# stm32.net
KiCad netlist of a schematic drawn in Altium Designer
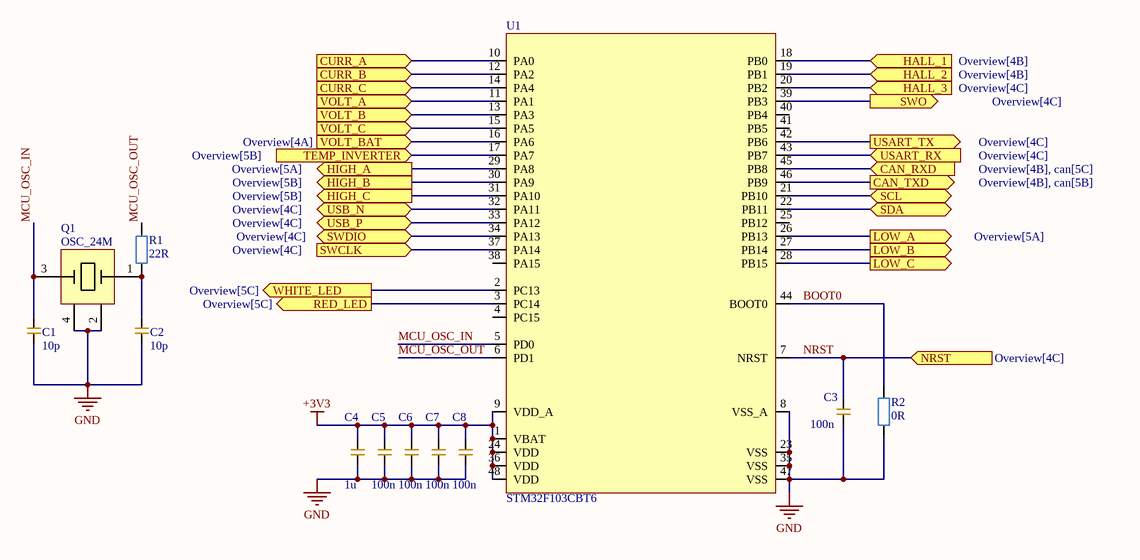
[diagram p0: stm32.SchDoc]

(export (version "E")
  (design (tool "Eeschema 10.0.6"))
  (components
    (comp (ref "C1")
      (value "10p")
      (footprint "CAP_0603")
      (description "Multilayer Ceramic Capacitors MLCC - SMD/SMT ROHS")
      (libsource (lib "Passive") (part "CAP_0603"))
    )
    (comp (ref "C2")
      (value "10p")
      (footprint "CAP_0603")
      (description "Multilayer Ceramic Capacitors MLCC - SMD/SMT ROHS")
      (libsource (lib "Passive") (part "CAP_0603"))
    )
    (comp (ref "C3")
      (value "100n")
      (footprint "CAP_0603")
      (description "Multilayer Ceramic Capacitors MLCC - SMD/SMT ROHS")
      (libsource (lib "Passive") (part "CAP_0603"))
    )
    (comp (ref "C4")
      (value "1u")
      (footprint "CAP_0603")
      (description "Multilayer Ceramic Capacitors MLCC - SMD/SMT ROHS")
      (libsource (lib "Passive") (part "CAP_0603"))
    )
    (comp (ref "C5")
      (value "100n")
      (footprint "CAP_0603")
      (description "Multilayer Ceramic Capacitors MLCC - SMD/SMT ROHS")
      (libsource (lib "Passive") (part "CAP_0603"))
    )
    (comp (ref "C6")
      (value "100n")
      (footprint "CAP_0603")
      (description "Multilayer Ceramic Capacitors MLCC - SMD/SMT ROHS")
      (libsource (lib "Passive") (part "CAP_0603"))
    )
    (comp (ref "C7")
      (value "100n")
      (footprint "CAP_0603")
      (description "Multilayer Ceramic Capacitors MLCC - SMD/SMT ROHS")
      (libsource (lib "Passive") (part "CAP_0603"))
    )
    (comp (ref "C8")
      (value "100n")
      (footprint "CAP_0603")
      (description "Multilayer Ceramic Capacitors MLCC - SMD/SMT ROHS")
      (libsource (lib "Passive") (part "CAP_0603"))
    )
    (comp (ref "Q1")
      (value "OSC_24M")
      (footprint "OSC_24M")
      (description "Crystal 24Mhz")
      (fields (field (name "MANUFACTURER PART") "X322524MOB4SI"))
      (libsource (lib "ICs") (part "OSC_24M"))
    )
    (comp (ref "R1")
      (value "22R")
      (footprint "RES_0603")
      (description "100mW Thick Film Resistors")
      (libsource (lib "Passive") (part "RES_0603"))
    )
    (comp (ref "R2")
      (value "0R")
      (footprint "RES_0603")
      (description "100mW Thick Film Resistors")
      (libsource (lib "Passive") (part "RES_0603"))
    )
    (comp (ref "U1")
      (value "STM32F103CBT6")
      (footprint "STM32F103CBT6")
      (fields (field (name "MFR.") "STMicroelectronics"))
      (libsource (lib "ICs") (part "STM32F103CBT6"))
    )
  )
  (nets
    (net (code "1") (name "+3V3") (class "Default")
      (node (ref "C4") (pin "2") (pintype "passive"))
      (node (ref "C5") (pin "2") (pintype "passive"))
      (node (ref "C6") (pin "2") (pintype "passive"))
      (node (ref "C7") (pin "2") (pintype "passive"))
      (node (ref "C8") (pin "2") (pintype "passive"))
      (node (ref "U1") (pin "1") (pinfunction "VBAT_1") (pintype "passive"))
      (node (ref "U1") (pin "24") (pinfunction "VDD_24") (pintype "passive"))
      (node (ref "U1") (pin "36") (pinfunction "VDD_36") (pintype "passive"))
      (node (ref "U1") (pin "48") (pinfunction "VDD_48") (pintype "passive"))
      (node (ref "U1") (pin "9") (pinfunction "VDD_A_9") (pintype "passive"))
    )
    (net (code "2") (name "/BOOT0") (class "Default")
      (node (ref "R2") (pin "2") (pintype "passive"))
      (node (ref "U1") (pin "44") (pinfunction "BOOT0_44") (pintype "passive"))
    )
    (net (code "3") (name "/CAN_RXD") (class "Default")
      (node (ref "U1") (pin "45") (pinfunction "PB8_45") (pintype "passive"))
    )
    (net (code "4") (name "/CAN_TXD") (class "Default")
      (node (ref "U1") (pin "46") (pinfunction "PB9_46") (pintype "passive"))
    )
    (net (code "5") (name "/CURR_A") (class "Default")
      (node (ref "U1") (pin "10") (pinfunction "PA0_10") (pintype "passive"))
    )
    (net (code "6") (name "/CURR_B") (class "Default")
      (node (ref "U1") (pin "12") (pinfunction "PA2_12") (pintype "passive"))
    )
    (net (code "7") (name "/CURR_C") (class "Default")
      (node (ref "U1") (pin "14") (pinfunction "PA4_14") (pintype "passive"))
    )
    (net (code "8") (name "/HALL_1") (class "Default")
      (node (ref "U1") (pin "18") (pinfunction "PB0_18") (pintype "passive"))
    )
    (net (code "9") (name "/HALL_2") (class "Default")
      (node (ref "U1") (pin "19") (pinfunction "PB1_19") (pintype "passive"))
    )
    (net (code "10") (name "/HALL_3") (class "Default")
      (node (ref "U1") (pin "20") (pinfunction "PB2_20") (pintype "passive"))
    )
    (net (code "11") (name "/HIGH_A") (class "Default")
      (node (ref "U1") (pin "29") (pinfunction "PA8_29") (pintype "passive"))
    )
    (net (code "12") (name "/HIGH_B") (class "Default")
      (node (ref "U1") (pin "30") (pinfunction "PA9_30") (pintype "passive"))
    )
    (net (code "13") (name "/HIGH_C") (class "Default")
      (node (ref "U1") (pin "31") (pinfunction "PA10_31") (pintype "passive"))
    )
    (net (code "14") (name "/LOW_A") (class "Default")
      (node (ref "U1") (pin "26") (pinfunction "PB13_26") (pintype "passive"))
    )
    (net (code "15") (name "/LOW_B") (class "Default")
      (node (ref "U1") (pin "27") (pinfunction "PB14_27") (pintype "passive"))
    )
    (net (code "16") (name "/LOW_C") (class "Default")
      (node (ref "U1") (pin "28") (pinfunction "PB15_28") (pintype "passive"))
    )
    (net (code "17") (name "/MCU_OSC_IN") (class "Default")
      (node (ref "C1") (pin "2") (pintype "passive"))
      (node (ref "Q1") (pin "3") (pintype "passive"))
      (node (ref "U1") (pin "5") (pinfunction "PD0_5") (pintype "passive"))
    )
    (net (code "18") (name "/MCU_OSC_OUT") (class "Default")
      (node (ref "R1") (pin "2") (pintype "passive"))
      (node (ref "U1") (pin "6") (pinfunction "PD1_6") (pintype "passive"))
    )
    (net (code "19") (name "/NRST") (class "Default")
      (node (ref "C3") (pin "2") (pintype "passive"))
      (node (ref "U1") (pin "7") (pinfunction "NRST_7") (pintype "passive"))
    )
    (net (code "20") (name "/RED_LED") (class "Default")
      (node (ref "U1") (pin "3") (pinfunction "PC14_3") (pintype "passive"))
    )
    (net (code "21") (name "/SCL") (class "Default")
      (node (ref "U1") (pin "21") (pinfunction "PB10_21") (pintype "passive"))
    )
    (net (code "22") (name "/SDA") (class "Default")
      (node (ref "U1") (pin "22") (pinfunction "PB11_22") (pintype "passive"))
    )
    (net (code "23") (name "/SWCLK") (class "Default")
      (node (ref "U1") (pin "37") (pinfunction "PA14_37") (pintype "passive"))
    )
    (net (code "24") (name "/SWDIO") (class "Default")
      (node (ref "U1") (pin "34") (pinfunction "PA13_34") (pintype "passive"))
    )
    (net (code "25") (name "/SWO") (class "Default")
      (node (ref "U1") (pin "39") (pinfunction "PB3_39") (pintype "passive"))
    )
    (net (code "26") (name "/TEMP_INVERTER") (class "Default")
      (node (ref "U1") (pin "17") (pinfunction "PA7_17") (pintype "passive"))
    )
    (net (code "27") (name "/USART_RX") (class "Default")
      (node (ref "U1") (pin "43") (pinfunction "PB7_43") (pintype "passive"))
    )
    (net (code "28") (name "/USART_TX") (class "Default")
      (node (ref "U1") (pin "42") (pinfunction "PB6_42") (pintype "passive"))
    )
    (net (code "29") (name "/USB_N") (class "Default")
      (node (ref "U1") (pin "32") (pinfunction "PA11_32") (pintype "passive"))
    )
    (net (code "30") (name "/USB_P") (class "Default")
      (node (ref "U1") (pin "33") (pinfunction "PA12_33") (pintype "passive"))
    )
    (net (code "31") (name "/VOLT_A") (class "Default")
      (node (ref "U1") (pin "11") (pinfunction "PA1_11") (pintype "passive"))
    )
    (net (code "32") (name "/VOLT_B") (class "Default")
      (node (ref "U1") (pin "13") (pinfunction "PA3_13") (pintype "passive"))
    )
    (net (code "33") (name "/VOLT_BAT") (class "Default")
      (node (ref "U1") (pin "16") (pinfunction "PA6_16") (pintype "passive"))
    )
    (net (code "34") (name "/VOLT_C") (class "Default")
      (node (ref "U1") (pin "15") (pinfunction "PA5_15") (pintype "passive"))
    )
    (net (code "35") (name "/WHITE_LED") (class "Default")
      (node (ref "U1") (pin "2") (pinfunction "PC13_2") (pintype "passive"))
    )
    (net (code "36") (name "GND") (class "Default")
      (node (ref "C1") (pin "1") (pintype "passive"))
      (node (ref "C2") (pin "1") (pintype "passive"))
      (node (ref "C3") (pin "1") (pintype "passive"))
      (node (ref "C4") (pin "1") (pintype "passive"))
      (node (ref "C5") (pin "1") (pintype "passive"))
      (node (ref "C6") (pin "1") (pintype "passive"))
      (node (ref "C7") (pin "1") (pintype "passive"))
      (node (ref "C8") (pin "1") (pintype "passive"))
      (node (ref "Q1") (pin "2") (pintype "passive"))
      (node (ref "Q1") (pin "4") (pintype "passive"))
      (node (ref "R2") (pin "1") (pintype "passive"))
      (node (ref "U1") (pin "23") (pinfunction "VSS_23") (pintype "passive"))
      (node (ref "U1") (pin "35") (pinfunction "VSS_35") (pintype "passive"))
      (node (ref "U1") (pin "47") (pinfunction "VSS_47") (pintype "passive"))
      (node (ref "U1") (pin "8") (pinfunction "VSS_A_8") (pintype "passive"))
    )
    (net (code "37") (name "Net-(C2-Pad2)") (class "Default")
      (node (ref "C2") (pin "2") (pintype "passive"))
      (node (ref "Q1") (pin "1") (pintype "passive"))
      (node (ref "R1") (pin "1") (pintype "passive"))
    )
    (net (code "38") (name "unconnected-(U1-PA15-Pad38)") (class "Default")
      (node (ref "U1") (pin "38") (pinfunction "PA15_38") (pintype "passive"))
    )
    (net (code "39") (name "unconnected-(U1-PB4-Pad40)") (class "Default")
      (node (ref "U1") (pin "40") (pinfunction "PB4_40") (pintype "passive"))
    )
    (net (code "40") (name "unconnected-(U1-PB5-Pad41)") (class "Default")
      (node (ref "U1") (pin "41") (pinfunction "PB5_41") (pintype "passive"))
    )
    (net (code "41") (name "unconnected-(U1-PB12-Pad25)") (class "Default")
      (node (ref "U1") (pin "25") (pinfunction "PB12_25") (pintype "passive"))
    )
    (net (code "42") (name "unconnected-(U1-PC15-Pad4)") (class "Default")
      (node (ref "U1") (pin "4") (pinfunction "PC15_4") (pintype "passive"))
    )
  )
)
